# ARDUINO_extension_connectors.net
KiCad netlist of a schematic drawn in Altium Designer
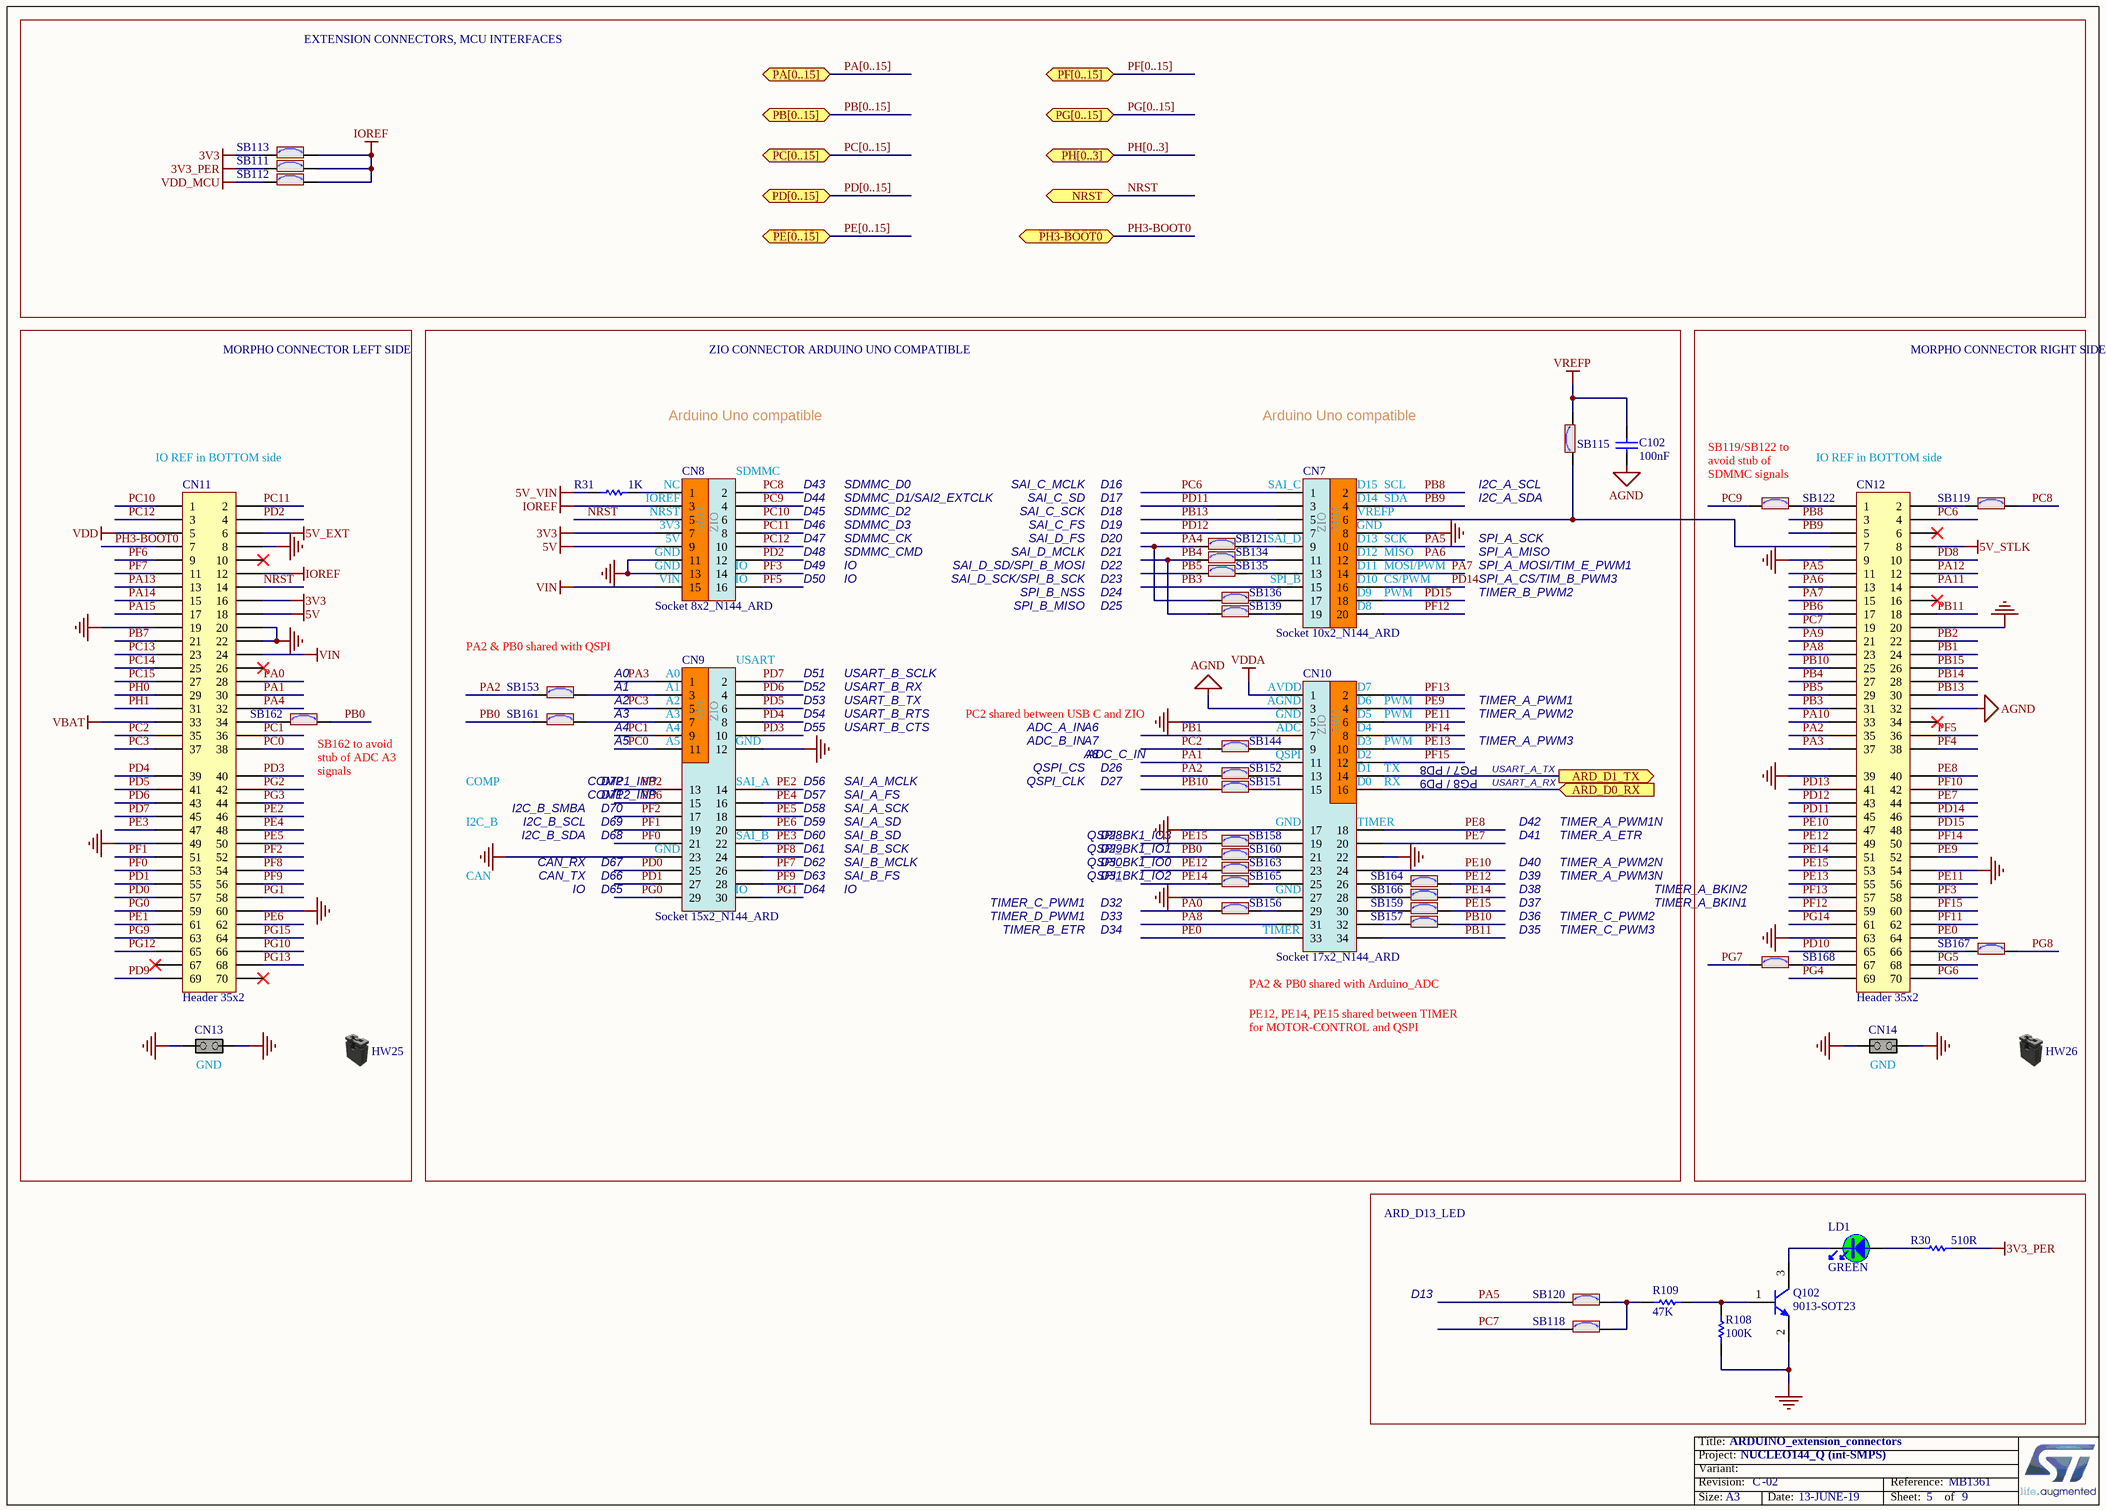
[diagram p0: ARDUINO_extension_connectors.SchDoc]

(export (version "E")
  (design (tool "Eeschema 10.0.6"))
  (components
    (comp (ref "C102")
      (value "100nF")
      (footprint "C0603")
      (description "Capacitor, MLCC, 100nF, 16V, X7R, 10%, 0603, T=0,8mm")
      (fields
        (field (name "INTERNAL_PART_NUMBER") "MCD-00211")
        (field (name "MANUFACTURER_PART_NUMBER") "CC0603KRX7R7BB104")
        (field (name "PROVIDED_BY") "Subcon")
      )
      (libsource (lib "MCD_PARTS_database") (part "Capacitor"))
    )
    (comp (ref "CN7")
      (value "Socket 10x2_N144_ARD")
      (footprint "CON_SAMTEC_SSW-110-23-X-D_N144_ARD")
      (description "Socket, 10x2, 2.54mm, VR, TH, Height 8.51mm/10mm, Low insertion force.")
      (fields
        (field (name "INTERNAL_PART_NUMBER") "MCD-01039")
        (field (name "MANUFACTURER_PART_NUMBER") "SSW-110-23-x-D")
        (field (name "PROVIDED_BY") "Subcon")
      )
      (libsource (lib "MCD_PARTS_database") (part "Socket 10x2_N144_ARD"))
    )
    (comp (ref "CN8")
      (value "Socket 8x2_N144_ARD")
      (footprint "CON_SAMTEC_SSW-108-23-X-D_N144_ARD")
      (description "Socket, 8x2, 2.54mm, VR, TH, Height 8.51mm/10mm, Low insertion force.")
      (fields
        (field (name "INTERNAL_PART_NUMBER") "MCD-01037")
        (field (name "MANUFACTURER_PART_NUMBER") "SSW-108-23-x-D")
        (field (name "PROVIDED_BY") "Subcon")
      )
      (libsource (lib "MCD_PARTS_database") (part "Socket 8x2_N144_ARD"))
    )
    (comp (ref "CN9")
      (value "Socket 15x2_N144_ARD")
      (footprint "CON_SAMTEC_SSW-115-23-X-D_N144_ARD")
      (description "Socket, 15x2, 2.54mm, VR, TH, Height 8.51mm/10mm, Low insertion force.")
      (fields
        (field (name "INTERNAL_PART_NUMBER") "MCD-01040")
        (field (name "MANUFACTURER_PART_NUMBER") "SSW-115-23-x-D")
        (field (name "PROVIDED_BY") "Subcon")
      )
      (libsource (lib "MCD_PARTS_database") (part "Socket 15x2_N144_ARD"))
    )
    (comp (ref "CN10")
      (value "Socket 17x2_N144_ARD")
      (footprint "CON_SAMTEC_SSW-117-23-X-D_N144_ARD")
      (description "Socket, 17x2, 2.54mm, VR, TH, Height 8.51mm/10mm, Low insertion force")
      (fields
        (field (name "INTERNAL_PART_NUMBER") "MCD-01041")
        (field (name "MANUFACTURER_PART_NUMBER") "SSW-117-23-x-D")
        (field (name "PROVIDED_BY") "Subcon")
      )
      (libsource (lib "MCD_PARTS_database") (part "Socket 17x2_N144_ARD"))
    )
    (comp (ref "CN11")
      (value "Header 35x2")
      (footprint "CON_SAMTEC_TSW-135-07-X-D")
      (description "Header, 35x2, 2,54mm, VR, TH, Height 5.84mm/2.54mm")
      (fields
        (field (name "INTERNAL_PART_NUMBER") "MCD-01210")
        (field (name "MANUFACTURER_PART_NUMBER") "TSW-135-07-x-D")
        (field (name "PROVIDED_BY") "Subcon")
      )
      (libsource (lib "MCD_PARTS_database") (part "Header 35x2"))
    )
    (comp (ref "CN12")
      (value "Header 35x2")
      (footprint "CON_SAMTEC_TSW-135-07-X-D")
      (description "Header, 35x2, 2,54mm, VR, TH, Height 5.84mm/2.54mm")
      (fields
        (field (name "INTERNAL_PART_NUMBER") "MCD-01210")
        (field (name "MANUFACTURER_PART_NUMBER") "TSW-135-07-x-D")
        (field (name "PROVIDED_BY") "Subcon")
      )
      (libsource (lib "MCD_PARTS_database") (part "Header 35x2"))
    )
    (comp (ref "CN13")
      (value "~")
      (footprint "CON_SAMTEC_TSW-102-09-X-S")
      (description "Header, 2x1, 2,54mm, VR, TH, Height 5.84mm/10.16mm")
      (fields
        (field (name "INTERNAL_PART_NUMBER") "MCD-00214")
        (field (name "MANUFACTURER_PART_NUMBER") "TSW-102-09-x-S")
        (field (name "PROVIDED_BY") "Subcon")
      )
      (libsource (lib "MCD_PARTS_database") (part "Jumper_Header 2x1"))
    )
    (comp (ref "CN14")
      (value "~")
      (footprint "CON_SAMTEC_TSW-102-09-X-S")
      (description "Header, 2x1, 2,54mm, VR, TH, Height 5.84mm/10.16mm")
      (fields
        (field (name "INTERNAL_PART_NUMBER") "MCD-00214")
        (field (name "MANUFACTURER_PART_NUMBER") "TSW-102-09-x-S")
        (field (name "PROVIDED_BY") "Subcon")
      )
      (libsource (lib "MCD_PARTS_database") (part "Jumper_Header 2x1"))
    )
    (comp (ref "HW25")
      (value "~")
      (description "SHUNT 2.54mm BLACK")
      (fields
        (field (name "INTERNAL_PART_NUMBER") "MCD-00043")
        (field (name "MANUFACTURER_PART_NUMBER") "SNT-100-BK-G")
        (field (name "PROVIDED_BY") "Subcon")
      )
      (libsource (lib "MCD_PARTS_database") (part "Shunt Black 2.54mm"))
    )
    (comp (ref "HW26")
      (value "~")
      (description "SHUNT 2.54mm BLACK")
      (fields
        (field (name "INTERNAL_PART_NUMBER") "MCD-00043")
        (field (name "MANUFACTURER_PART_NUMBER") "SNT-100-BK-G")
        (field (name "PROVIDED_BY") "Subcon")
      )
      (libsource (lib "MCD_PARTS_database") (part "Shunt Black 2.54mm"))
    )
    (comp (ref "LD1")
      (value "GREEN")
      (footprint "LED_0603_GREEN")
      (description "LED, Green, 0603")
      (fields
        (field (name "INTERNAL_PART_NUMBER") "MCD-00050")
        (field (name "MANUFACTURER_PART_NUMBER") "19-213SYGC/S530-E2/TR8")
        (field (name "PROVIDED_BY") "Subcon")
      )
      (libsource (lib "MCD_PARTS_database") (part "LED_green"))
    )
    (comp (ref "Q102")
      (value "9013-SOT23")
      (footprint "NPN_SOT23")
      (description "NPN Bipolar Transistor")
      (fields
        (field (name "INTERNAL_PART_NUMBER") "MCD-00073")
        (field (name "MANUFACTURER_PART_NUMBER") "BSR14")
        (field (name "PROVIDED_BY") "Subcon")
      )
      (libsource (lib "MCD_PARTS_database") (part "9013-SOT23"))
    )
    (comp (ref "R30")
      (value "510R")
      (footprint "R0603")
      (description "Resistor,510R,0603,1%,1/10W")
      (fields
        (field (name "INTERNAL_PART_NUMBER") "MCD-00225")
        (field (name "MANUFACTURER_PART_NUMBER") "RC0603FR-07510RL")
        (field (name "PROVIDED_BY") "Subcon")
      )
      (libsource (lib "MCD_PARTS_database") (part "Resistor"))
    )
    (comp (ref "R31")
      (value "1K")
      (footprint "R0603")
      (description "Resistor,1K,0603,1%,1/10W")
      (fields
        (field (name "INTERNAL_PART_NUMBER") "MCD-00070")
        (field (name "MANUFACTURER_PART_NUMBER") "RC0603FR-071KL")
        (field (name "PROVIDED_BY") "Subcon")
      )
      (libsource (lib "MCD_PARTS_database") (part "Resistor"))
    )
    (comp (ref "R108")
      (value "100K")
      (footprint "R0603")
      (description "Resistor,100K,0603,1%,1/10W")
      (fields
        (field (name "INTERNAL_PART_NUMBER") "MCD-00223")
        (field (name "MANUFACTURER_PART_NUMBER") "RC0603FR-07100KL")
        (field (name "PROVIDED_BY") "Subcon")
      )
      (libsource (lib "MCD_PARTS_database") (part "Resistor"))
    )
    (comp (ref "R109")
      (value "47K")
      (footprint "R0603")
      (description "Resistor,47K,0603,1%,1/10W")
      (fields
        (field (name "INTERNAL_PART_NUMBER") "MCD-00222")
        (field (name "MANUFACTURER_PART_NUMBER") "RC0603FR-0747KL")
        (field (name "PROVIDED_BY") "Subcon")
      )
      (libsource (lib "MCD_PARTS_database") (part "Resistor"))
    )
    (comp (ref "SB111")
      (value "~")
      (footprint "SOLDER-BRIDGE_R0603-0R")
      (description "Solder Bridge ON")
      (fields (field (name "INTERNAL_PART_NUMBER") "MCD-00071") (field (name "PROVIDED_BY") "Subcon"))
      (libsource (lib "MCD_PARTS_database") (part "SB_ON"))
    )
    (comp (ref "SB112")
      (value "~")
      (footprint "SOLDER-BRIDGE_R0603-0R")
      (description "Solder Bridge ON")
      (fields (field (name "INTERNAL_PART_NUMBER") "MCD-00071") (field (name "PROVIDED_BY") "Subcon"))
      (libsource (lib "MCD_PARTS_database") (part "SB_ON"))
    )
    (comp (ref "SB113")
      (value "~")
      (footprint "SOLDER-BRIDGE_R0603-0R")
      (description "Solder Bridge ON")
      (fields (field (name "INTERNAL_PART_NUMBER") "MCD-00071") (field (name "PROVIDED_BY") "Subcon"))
      (libsource (lib "MCD_PARTS_database") (part "SB_ON"))
    )
    (comp (ref "SB115")
      (value "~")
      (footprint "SOLDER-BRIDGE_R0603-0R")
      (description "Solder Bridge ON")
      (fields (field (name "INTERNAL_PART_NUMBER") "MCD-00071") (field (name "PROVIDED_BY") "Subcon"))
      (libsource (lib "") (part "SB_ON_1"))
    )
    (comp (ref "SB118")
      (value "~")
      (footprint "SOLDER-BRIDGE_R0603-0R")
      (description "Solder Bridge ON")
      (fields (field (name "INTERNAL_PART_NUMBER") "MCD-00071") (field (name "PROVIDED_BY") "Subcon"))
      (libsource (lib "MCD_PARTS_database") (part "SB_ON"))
    )
    (comp (ref "SB119")
      (value "~")
      (footprint "SOLDER-BRIDGE_R0603-0R")
      (description "Solder Bridge ON")
      (fields (field (name "INTERNAL_PART_NUMBER") "MCD-00071") (field (name "PROVIDED_BY") "Subcon"))
      (libsource (lib "MCD_PARTS_database") (part "SB_ON"))
    )
    (comp (ref "SB120")
      (value "~")
      (footprint "SOLDER-BRIDGE_R0603-0R")
      (description "Solder Bridge ON")
      (fields (field (name "INTERNAL_PART_NUMBER") "MCD-00071") (field (name "PROVIDED_BY") "Subcon"))
      (libsource (lib "MCD_PARTS_database") (part "SB_ON"))
    )
    (comp (ref "SB121")
      (value "~")
      (footprint "SOLDER-BRIDGE_R0603-0R")
      (description "Solder Bridge ON")
      (fields (field (name "INTERNAL_PART_NUMBER") "MCD-00071") (field (name "PROVIDED_BY") "Subcon"))
      (libsource (lib "MCD_PARTS_database") (part "SB_ON"))
    )
    (comp (ref "SB122")
      (value "~")
      (footprint "SOLDER-BRIDGE_R0603-0R")
      (description "Solder Bridge ON")
      (fields (field (name "INTERNAL_PART_NUMBER") "MCD-00071") (field (name "PROVIDED_BY") "Subcon"))
      (libsource (lib "MCD_PARTS_database") (part "SB_ON"))
    )
    (comp (ref "SB134")
      (value "~")
      (footprint "SOLDER-BRIDGE_R0603-0R")
      (description "Solder Bridge ON")
      (fields (field (name "INTERNAL_PART_NUMBER") "MCD-00071") (field (name "PROVIDED_BY") "Subcon"))
      (libsource (lib "MCD_PARTS_database") (part "SB_ON"))
    )
    (comp (ref "SB135")
      (value "~")
      (footprint "SOLDER-BRIDGE_R0603-0R")
      (description "Solder Bridge ON")
      (fields (field (name "INTERNAL_PART_NUMBER") "MCD-00071") (field (name "PROVIDED_BY") "Subcon"))
      (libsource (lib "MCD_PARTS_database") (part "SB_ON"))
    )
    (comp (ref "SB136")
      (value "~")
      (footprint "SOLDER-BRIDGE_R0603-0R")
      (description "Solder Bridge ON")
      (fields (field (name "INTERNAL_PART_NUMBER") "MCD-00071") (field (name "PROVIDED_BY") "Subcon"))
      (libsource (lib "MCD_PARTS_database") (part "SB_ON"))
    )
    (comp (ref "SB139")
      (value "~")
      (footprint "SOLDER-BRIDGE_R0603-0R")
      (description "Solder Bridge ON")
      (fields (field (name "INTERNAL_PART_NUMBER") "MCD-00071") (field (name "PROVIDED_BY") "Subcon"))
      (libsource (lib "MCD_PARTS_database") (part "SB_ON"))
    )
    (comp (ref "SB144")
      (value "~")
      (footprint "SOLDER-BRIDGE_R0603-0R")
      (description "Solder Bridge ON")
      (fields (field (name "INTERNAL_PART_NUMBER") "MCD-00071") (field (name "PROVIDED_BY") "Subcon"))
      (libsource (lib "MCD_PARTS_database") (part "SB_ON"))
    )
    (comp (ref "SB151")
      (value "~")
      (footprint "SOLDER-BRIDGE_R0603-0R")
      (description "Solder Bridge ON")
      (fields (field (name "INTERNAL_PART_NUMBER") "MCD-00071") (field (name "PROVIDED_BY") "Subcon"))
      (libsource (lib "MCD_PARTS_database") (part "SB_ON"))
    )
    (comp (ref "SB152")
      (value "~")
      (footprint "SOLDER-BRIDGE_R0603-0R")
      (description "Solder Bridge ON")
      (fields (field (name "INTERNAL_PART_NUMBER") "MCD-00071") (field (name "PROVIDED_BY") "Subcon"))
      (libsource (lib "MCD_PARTS_database") (part "SB_ON"))
    )
    (comp (ref "SB153")
      (value "~")
      (footprint "SOLDER-BRIDGE_R0603-0R")
      (description "Solder Bridge ON")
      (fields (field (name "INTERNAL_PART_NUMBER") "MCD-00071") (field (name "PROVIDED_BY") "Subcon"))
      (libsource (lib "MCD_PARTS_database") (part "SB_ON"))
    )
    (comp (ref "SB156")
      (value "~")
      (footprint "SOLDER-BRIDGE_R0603-0R")
      (description "Solder Bridge ON")
      (fields (field (name "INTERNAL_PART_NUMBER") "MCD-00071") (field (name "PROVIDED_BY") "Subcon"))
      (libsource (lib "MCD_PARTS_database") (part "SB_ON"))
    )
    (comp (ref "SB157")
      (value "~")
      (footprint "SOLDER-BRIDGE_R0603-0R")
      (description "Solder Bridge ON")
      (fields (field (name "INTERNAL_PART_NUMBER") "MCD-00071") (field (name "PROVIDED_BY") "Subcon"))
      (libsource (lib "MCD_PARTS_database") (part "SB_ON"))
    )
    (comp (ref "SB158")
      (value "~")
      (footprint "SOLDER-BRIDGE_R0603-0R")
      (description "Solder Bridge ON")
      (fields (field (name "INTERNAL_PART_NUMBER") "MCD-00071") (field (name "PROVIDED_BY") "Subcon"))
      (libsource (lib "MCD_PARTS_database") (part "SB_ON"))
    )
    (comp (ref "SB159")
      (value "~")
      (footprint "SOLDER-BRIDGE_R0603-0R")
      (description "Solder Bridge ON")
      (fields (field (name "INTERNAL_PART_NUMBER") "MCD-00071") (field (name "PROVIDED_BY") "Subcon"))
      (libsource (lib "MCD_PARTS_database") (part "SB_ON"))
    )
    (comp (ref "SB160")
      (value "~")
      (footprint "SOLDER-BRIDGE_R0603-0R")
      (description "Solder Bridge ON")
      (fields (field (name "INTERNAL_PART_NUMBER") "MCD-00071") (field (name "PROVIDED_BY") "Subcon"))
      (libsource (lib "MCD_PARTS_database") (part "SB_ON"))
    )
    (comp (ref "SB161")
      (value "~")
      (footprint "SOLDER-BRIDGE_R0603-0R")
      (description "Solder Bridge ON")
      (fields (field (name "INTERNAL_PART_NUMBER") "MCD-00071") (field (name "PROVIDED_BY") "Subcon"))
      (libsource (lib "MCD_PARTS_database") (part "SB_ON"))
    )
    (comp (ref "SB162")
      (value "~")
      (footprint "SOLDER-BRIDGE_R0603-0R")
      (description "Solder Bridge ON")
      (fields (field (name "INTERNAL_PART_NUMBER") "MCD-00071") (field (name "PROVIDED_BY") "Subcon"))
      (libsource (lib "MCD_PARTS_database") (part "SB_ON"))
    )
    (comp (ref "SB163")
      (value "~")
      (footprint "SOLDER-BRIDGE_R0603-0R")
      (description "Solder Bridge ON")
      (fields (field (name "INTERNAL_PART_NUMBER") "MCD-00071") (field (name "PROVIDED_BY") "Subcon"))
      (libsource (lib "MCD_PARTS_database") (part "SB_ON"))
    )
    (comp (ref "SB164")
      (value "~")
      (footprint "SOLDER-BRIDGE_R0603-0R")
      (description "Solder Bridge ON")
      (fields (field (name "INTERNAL_PART_NUMBER") "MCD-00071") (field (name "PROVIDED_BY") "Subcon"))
      (libsource (lib "MCD_PARTS_database") (part "SB_ON"))
    )
    (comp (ref "SB165")
      (value "~")
      (footprint "SOLDER-BRIDGE_R0603-0R")
      (description "Solder Bridge ON")
      (fields (field (name "INTERNAL_PART_NUMBER") "MCD-00071") (field (name "PROVIDED_BY") "Subcon"))
      (libsource (lib "MCD_PARTS_database") (part "SB_ON"))
    )
    (comp (ref "SB166")
      (value "~")
      (footprint "SOLDER-BRIDGE_R0603-0R")
      (description "Solder Bridge ON")
      (fields (field (name "INTERNAL_PART_NUMBER") "MCD-00071") (field (name "PROVIDED_BY") "Subcon"))
      (libsource (lib "MCD_PARTS_database") (part "SB_ON"))
    )
    (comp (ref "SB167")
      (value "~")
      (footprint "SOLDER-BRIDGE_R0603-0R")
      (description "Solder Bridge ON")
      (fields (field (name "INTERNAL_PART_NUMBER") "MCD-00071") (field (name "PROVIDED_BY") "Subcon"))
      (libsource (lib "MCD_PARTS_database") (part "SB_ON"))
    )
    (comp (ref "SB168")
      (value "~")
      (footprint "SOLDER-BRIDGE_R0603-0R")
      (description "Solder Bridge ON")
      (fields (field (name "INTERNAL_PART_NUMBER") "MCD-00071") (field (name "PROVIDED_BY") "Subcon"))
      (libsource (lib "MCD_PARTS_database") (part "SB_ON"))
    )
  )
  (nets
    (net (code "7") (name "/ARD_D0_RX") (class "Default")
      (node (ref "CN10") (pin "16") (pinfunction "16_16") (pintype "passive"))
    )
    (net (code "8") (name "/ARD_D1_TX") (class "Default")
      (node (ref "CN10") (pin "14") (pinfunction "14_14") (pintype "passive"))
    )
    (net (code "9") (name "/NRST") (class "Default")
      (node (ref "CN11") (pin "14") (pinfunction "14_14") (pintype "passive"))
      (node (ref "CN8") (pin "5") (pinfunction "5_5") (pintype "passive"))
    )
    (net (code "10") (name "/PA0") (class "Default")
      (node (ref "CN11") (pin "28") (pinfunction "28_28") (pintype "passive"))
      (node (ref "SB156") (pin "1") (pinfunction "1_1") (pintype "passive"))
    )
    (net (code "11") (name "/PA1") (class "Default")
      (node (ref "CN10") (pin "11") (pinfunction "11_11") (pintype "passive"))
      (node (ref "CN11") (pin "30") (pinfunction "30_30") (pintype "passive"))
    )
    (net (code "12") (name "/PA2") (class "Default")
      (node (ref "CN12") (pin "35") (pinfunction "35_35") (pintype "passive"))
      (node (ref "SB152") (pin "1") (pinfunction "1_1") (pintype "passive"))
      (node (ref "SB153") (pin "1") (pinfunction "1_1") (pintype "passive"))
    )
    (net (code "13") (name "/PA3") (class "Default")
      (node (ref "CN12") (pin "37") (pinfunction "37_37") (pintype "passive"))
      (node (ref "CN9") (pin "1") (pinfunction "1_1") (pintype "passive"))
    )
    (net (code "14") (name "/PA4") (class "Default")
      (node (ref "CN11") (pin "32") (pinfunction "32_32") (pintype "passive"))
      (node (ref "SB121") (pin "1") (pinfunction "1_1") (pintype "passive"))
      (node (ref "SB136") (pin "1") (pinfunction "1_1") (pintype "passive"))
    )
    (net (code "15") (name "/PA5") (class "Default")
      (node (ref "CN12") (pin "11") (pinfunction "11_11") (pintype "passive"))
      (node (ref "CN7") (pin "10") (pinfunction "10_10") (pintype "passive"))
      (node (ref "SB120") (pin "1") (pinfunction "1_1") (pintype "passive"))
    )
    (net (code "16") (name "/PA6") (class "Default")
      (node (ref "CN12") (pin "13") (pinfunction "13_13") (pintype "passive"))
      (node (ref "CN7") (pin "12") (pinfunction "12_12") (pintype "passive"))
    )
    (net (code "17") (name "/PA7") (class "Default")
      (node (ref "CN12") (pin "15") (pinfunction "15_15") (pintype "passive"))
      (node (ref "CN7") (pin "14") (pinfunction "14_14") (pintype "passive"))
    )
    (net (code "18") (name "/PA8") (class "Default")
      (node (ref "CN10") (pin "31") (pinfunction "31_31") (pintype "passive"))
      (node (ref "CN12") (pin "23") (pinfunction "23_23") (pintype "passive"))
    )
    (net (code "19") (name "/PA9") (class "Default")
      (node (ref "CN12") (pin "21") (pinfunction "21_21") (pintype "passive"))
    )
    (net (code "20") (name "/PA10") (class "Default")
      (node (ref "CN12") (pin "33") (pinfunction "33_33") (pintype "passive"))
    )
    (net (code "21") (name "/PA11") (class "Default")
      (node (ref "CN12") (pin "14") (pinfunction "14_14") (pintype "passive"))
    )
    (net (code "22") (name "/PA12") (class "Default")
      (node (ref "CN12") (pin "12") (pinfunction "12_12") (pintype "passive"))
    )
    (net (code "23") (name "/PA13") (class "Default")
      (node (ref "CN11") (pin "13") (pinfunction "13_13") (pintype "passive"))
    )
    (net (code "24") (name "/PA14") (class "Default")
      (node (ref "CN11") (pin "15") (pinfunction "15_15") (pintype "passive"))
    )
    (net (code "25") (name "/PA15") (class "Default")
      (node (ref "CN11") (pin "17") (pinfunction "17_17") (pintype "passive"))
    )
    (net (code "27") (name "/PB0") (class "Default")
      (node (ref "SB160") (pin "1") (pinfunction "1_1") (pintype "passive"))
      (node (ref "SB161") (pin "1") (pinfunction "1_1") (pintype "passive"))
      (node (ref "SB162") (pin "2") (pinfunction "2_2") (pintype "passive"))
    )
    (net (code "28") (name "/PB1") (class "Default")
      (node (ref "CN10") (pin "7") (pinfunction "7_7") (pintype "passive"))
      (node (ref "CN12") (pin "24") (pinfunction "24_24") (pintype "passive"))
    )
    (net (code "29") (name "/PB2") (class "Default")
      (node (ref "CN12") (pin "22") (pinfunction "22_22") (pintype "passive"))
      (node (ref "CN9") (pin "13") (pinfunction "13_13") (pintype "passive"))
    )
    (net (code "30") (name "/PB3") (class "Default")
      (node (ref "CN12") (pin "31") (pinfunction "31_31") (pintype "passive"))
      (node (ref "CN7") (pin "15") (pinfunction "15_15") (pintype "passive"))
    )
    (net (code "31") (name "/PB4") (class "Default")
      (node (ref "CN12") (pin "27") (pinfunction "27_27") (pintype "passive"))
      (node (ref "SB134") (pin "1") (pinfunction "1_1") (pintype "passive"))
      (node (ref "SB139") (pin "1") (pinfunction "1_1") (pintype "passive"))
    )
    (net (code "32") (name "/PB5") (class "Default")
      (node (ref "CN12") (pin "29") (pinfunction "29_29") (pintype "passive"))
      (node (ref "SB135") (pin "1") (pinfunction "1_1") (pintype "passive"))
    )
    (net (code "33") (name "/PB6") (class "Default")
      (node (ref "CN12") (pin "17") (pinfunction "17_17") (pintype "passive"))
      (node (ref "CN9") (pin "15") (pinfunction "15_15") (pintype "passive"))
    )
    (net (code "34") (name "/PB7") (class "Default")
      (node (ref "CN11") (pin "21") (pinfunction "21_21") (pintype "passive"))
    )
    (net (code "35") (name "/PB8") (class "Default")
      (node (ref "CN12") (pin "3") (pinfunction "3_3") (pintype "passive"))
      (node (ref "CN7") (pin "2") (pinfunction "2_2") (pintype "passive"))
    )
    (net (code "36") (name "/PB9") (class "Default")
      (node (ref "CN12") (pin "5") (pinfunction "5_5") (pintype "passive"))
      (node (ref "CN7") (pin "4") (pinfunction "4_4") (pintype "passive"))
    )
    (net (code "37") (name "/PB10") (class "Default")
      (node (ref "CN12") (pin "25") (pinfunction "25_25") (pintype "passive"))
      (node (ref "SB151") (pin "1") (pinfunction "1_1") (pintype "passive"))
      (node (ref "SB157") (pin "2") (pinfunction "2_2") (pintype "passive"))
    )
    (net (code "38") (name "/PB11") (class "Default")
      (node (ref "CN10") (pin "34") (pinfunction "34_34") (pintype "passive"))
      (node (ref "CN12") (pin "18") (pinfunction "18_18") (pintype "passive"))
    )
    (net (code "39") (name "/PB13") (class "Default")
      (node (ref "CN12") (pin "30") (pinfunction "30_30") (pintype "passive"))
      (node (ref "CN7") (pin "5") (pinfunction "5_5") (pintype "passive"))
    )
    (net (code "40") (name "/PB14") (class "Default")
      (node (ref "CN12") (pin "28") (pinfunction "28_28") (pintype "passive"))
    )
    (net (code "41") (name "/PB15") (class "Default")
      (node (ref "CN12") (pin "26") (pinfunction "26_26") (pintype "passive"))
    )
    (net (code "43") (name "/PC0") (class "Default")
      (node (ref "CN11") (pin "38") (pinfunction "38_38") (pintype "passive"))
      (node (ref "CN9") (pin "11") (pinfunction "11_11") (pintype "passive"))
    )
    (net (code "44") (name "/PC1") (class "Default")
      (node (ref "CN11") (pin "36") (pinfunction "36_36") (pintype "passive"))
      (node (ref "CN9") (pin "9") (pinfunction "9_9") (pintype "passive"))
    )
    (net (code "45") (name "/PC2") (class "Default")
      (node (ref "CN11") (pin "35") (pinfunction "35_35") (pintype "passive"))
      (node (ref "SB144") (pin "1") (pinfunction "1_1") (pintype "passive"))
    )
    (net (code "46") (name "/PC3") (class "Default")
      (node (ref "CN11") (pin "37") (pinfunction "37_37") (pintype "passive"))
      (node (ref "CN9") (pin "5") (pinfunction "5_5") (pintype "passive"))
    )
    (net (code "47") (name "/PC6") (class "Default")
      (node (ref "CN12") (pin "4") (pinfunction "4_4") (pintype "passive"))
      (node (ref "CN7") (pin "1") (pinfunction "1_1") (pintype "passive"))
    )
    (net (code "48") (name "/PC7") (class "Default")
      (node (ref "CN12") (pin "19") (pinfunction "19_19") (pintype "passive"))
      (node (ref "SB118") (pin "1") (pinfunction "1_1") (pintype "passive"))
    )
    (net (code "49") (name "/PC8") (class "Default")
      (node (ref "CN8") (pin "2") (pinfunction "2_2") (pintype "passive"))
      (node (ref "SB119") (pin "2") (pinfunction "2_2") (pintype "passive"))
    )
    (net (code "50") (name "/PC9") (class "Default")
      (node (ref "CN8") (pin "4") (pinfunction "4_4") (pintype "passive"))
      (node (ref "SB122") (pin "1") (pinfunction "1_1") (pintype "passive"))
    )
    (net (code "51") (name "/PC10") (class "Default")
      (node (ref "CN11") (pin "1") (pinfunction "1_1") (pintype "passive"))
      (node (ref "CN8") (pin "6") (pinfunction "6_6") (pintype "passive"))
    )
    (net (code "52") (name "/PC11") (class "Default")
      (node (ref "CN11") (pin "2") (pinfunction "2_2") (pintype "passive"))
      (node (ref "CN8") (pin "8") (pinfunction "8_8") (pintype "passive"))
    )
    (net (code "53") (name "/PC12") (class "Default")
      (node (ref "CN11") (pin "3") (pinfunction "3_3") (pintype "passive"))
      (node (ref "CN8") (pin "10") (pinfunction "10_10") (pintype "passive"))
    )
    (net (code "54") (name "/PC13") (class "Default")
      (node (ref "CN11") (pin "23") (pinfunction "23_23") (pintype "passive"))
    )
    (net (code "55") (name "/PC14") (class "Default")
      (node (ref "CN11") (pin "25") (pinfunction "25_25") (pintype "passive"))
    )
    (net (code "56") (name "/PC15") (class "Default")
      (node (ref "CN11") (pin "27") (pinfunction "27_27") (pintype "passive"))
    )
    (net (code "58") (name "/PD0") (class "Default")
      (node (ref "CN11") (pin "57") (pinfunction "57_57") (pintype "passive"))
      (node (ref "CN9") (pin "25") (pinfunction "25_25") (pintype "passive"))
    )
    (net (code "59") (name "/PD1") (class "Default")
      (node (ref "CN11") (pin "55") (pinfunction "55_55") (pintype "passive"))
      (node (ref "CN9") (pin "27") (pinfunction "27_27") (pintype "passive"))
    )
    (net (code "60") (name "/PD2") (class "Default")
      (node (ref "CN11") (pin "4") (pinfunction "4_4") (pintype "passive"))
      (node (ref "CN8") (pin "12") (pinfunction "12_12") (pintype "passive"))
    )
    (net (code "61") (name "/PD3") (class "Default")
      (node (ref "CN11") (pin "40") (pinfunction "40_40") (pintype "passive"))
      (node (ref "CN9") (pin "10") (pinfunction "10_10") (pintype "passive"))
    )
    (net (code "62") (name "/PD4") (class "Default")
      (node (ref "CN11") (pin "39") (pinfunction "39_39") (pintype "passive"))
      (node (ref "CN9") (pin "8") (pinfunction "8_8") (pintype "passive"))
    )
    (net (code "63") (name "/PD5") (class "Default")
      (node (ref "CN11") (pin "41") (pinfunction "41_41") (pintype "passive"))
      (node (ref "CN9") (pin "6") (pinfunction "6_6") (pintype "passive"))
    )
    (net (code "64") (name "/PD6") (class "Default")
      (node (ref "CN11") (pin "43") (pinfunction "43_43") (pintype "passive"))
      (node (ref "CN9") (pin "4") (pinfunction "4_4") (pintype "passive"))
    )
    (net (code "65") (name "/PD7") (class "Default")
      (node (ref "CN11") (pin "45") (pinfunction "45_45") (pintype "passive"))
      (node (ref "CN9") (pin "2") (pinfunction "2_2") (pintype "passive"))
    )
    (net (code "66") (name "/PD8") (class "Default")
      (node (ref "CN12") (pin "10") (pinfunction "10_10") (pintype "passive"))
    )
    (net (code "67") (name "/PD9") (class "Default")
      (node (ref "CN11") (pin "69") (pinfunction "69_69") (pintype "passive"))
    )
    (net (code "68") (name "/PD10") (class "Default")
      (node (ref "CN12") (pin "65") (pinfunction "65_65") (pintype "passive"))
    )
    (net (code "69") (name "/PD11") (class "Default")
      (node (ref "CN12") (pin "45") (pinfunction "45_45") (pintype "passive"))
      (node (ref "CN7") (pin "3") (pinfunction "3_3") (pintype "passive"))
    )
    (net (code "70") (name "/PD12") (class "Default")
      (node (ref "CN12") (pin "43") (pinfunction "43_43") (pintype "passive"))
      (node (ref "CN7") (pin "7") (pinfunction "7_7") (pintype "passive"))
    )
    (net (code "71") (name "/PD13") (class "Default")
      (node (ref "CN12") (pin "41") (pinfunction "41_41") (pintype "passive"))
    )
    (net (code "72") (name "/PD14") (class "Default")
      (node (ref "CN12") (pin "46") (pinfunction "46_46") (pintype "passive"))
      (node (ref "CN7") (pin "16") (pinfunction "16_16") (pintype "passive"))
    )
    (net (code "73") (name "/PD15") (class "Default")
      (node (ref "CN12") (pin "48") (pinfunction "48_48") (pintype "passive"))
      (node (ref "CN7") (pin "18") (pinfunction "18_18") (pintype "passive"))
    )
    (net (code "75") (name "/PE0") (class "Default")
      (node (ref "CN10") (pin "33") (pinfunction "33_33") (pintype "passive"))
      (node (ref "CN12") (pin "64") (pinfunction "64_64") (pintype "passive"))
    )
    (net (code "76") (name "/PE1") (class "Default")
      (node (ref "CN11") (pin "61") (pinfunction "61_61") (pintype "passive"))
    )
    (net (code "77") (name "/PE2") (class "Default")
      (node (ref "CN11") (pin "46") (pinfunction "46_46") (pintype "passive"))
      (node (ref "CN9") (pin "14") (pinfunction "14_14") (pintype "passive"))
    )
    (net (code "78") (name "/PE3") (class "Default")
      (node (ref "CN11") (pin "47") (pinfunction "47_47") (pintype "passive"))
      (node (ref "CN9") (pin "22") (pinfunction "22_22") (pintype "passive"))
    )
    (net (code "79") (name "/PE4") (class "Default")
      (node (ref "CN11") (pin "48") (pinfunction "48_48") (pintype "passive"))
      (node (ref "CN9") (pin "16") (pinfunction "16_16") (pintype "passive"))
    )
    (net (code "80") (name "/PE5") (class "Default")
      (node (ref "CN11") (pin "50") (pinfunction "50_50") (pintype "passive"))
      (node (ref "CN9") (pin "18") (pinfunction "18_18") (pintype "passive"))
    )
    (net (code "81") (name "/PE6") (class "Default")
      (node (ref "CN11") (pin "62") (pinfunction "62_62") (pintype "passive"))
      (node (ref "CN9") (pin "20") (pinfunction "20_20") (pintype "passive"))
    )
    (net (code "82") (name "/PE7") (class "Default")
      (node (ref "CN10") (pin "20") (pinfunction "20_20") (pintype "passive"))
      (node (ref "CN12") (pin "44") (pinfunction "44_44") (pintype "passive"))
    )
    (net (code "83") (name "/PE8") (class "Default")
      (node (ref "CN10") (pin "18") (pinfunction "18_18") (pintype "passive"))
      (node (ref "CN12") (pin "40") (pinfunction "40_40") (pintype "passive"))
    )
    (net (code "84") (name "/PE9") (class "Default")
      (node (ref "CN10") (pin "4") (pinfunction "4_4") (pintype "passive"))
      (node (ref "CN12") (pin "52") (pinfunction "52_52") (pintype "passive"))
    )
    (net (code "85") (name "/PE10") (class "Default")
      (node (ref "CN10") (pin "24") (pinfunction "24_24") (pintype "passive"))
      (node (ref "CN12") (pin "47") (pinfunction "47_47") (pintype "passive"))
    )
    (net (code "86") (name "/PE11") (class "Default")
      (node (ref "CN10") (pin "6") (pinfunction "6_6") (pintype "passive"))
      (node (ref "CN12") (pin "56") (pinfunction "56_56") (pintype "passive"))
    )
    (net (code "87") (name "/PE12") (class "Default")
      (node (ref "CN12") (pin "49") (pinfunction "49_49") (pintype "passive"))
      (node (ref "SB163") (pin "1") (pinfunction "1_1") (pintype "passive"))
      (node (ref "SB164") (pin "2") (pinfunction "2_2") (pintype "passive"))
    )
    (net (code "88") (name "/PE13") (class "Default")
      (node (ref "CN10") (pin "10") (pinfunction "10_10") (pintype "passive"))
      (node (ref "CN12") (pin "55") (pinfunction "55_55") (pintype "passive"))
    )
    (net (code "89") (name "/PE14") (class "Default")
      (node (ref "CN12") (pin "51") (pinfunction "51_51") (pintype "passive"))
      (node (ref "SB165") (pin "1") (pinfunction "1_1") (pintype "passive"))
      (node (ref "SB166") (pin "2") (pinfunction "2_2") (pintype "passive"))
    )
    (net (code "90") (name "/PE15") (class "Default")
      (node (ref "CN12") (pin "53") (pinfunction "53_53") (pintype "passive"))
      (node (ref "SB158") (pin "1") (pinfunction "1_1") (pintype "passive"))
      (node (ref "SB159") (pin "2") (pinfunction "2_2") (pintype "passive"))
    )
    (net (code "92") (name "/PF0") (class "Default")
      (node (ref "CN11") (pin "53") (pinfunction "53_53") (pintype "passive"))
      (node (ref "CN9") (pin "21") (pinfunction "21_21") (pintype "passive"))
    )
    (net (code "93") (name "/PF1") (class "Default")
      (node (ref "CN11") (pin "51") (pinfunction "51_51") (pintype "passive"))
      (node (ref "CN9") (pin "19") (pinfunction "19_19") (pintype "passive"))
    )
    (net (code "94") (name "/PF2") (class "Default")
      (node (ref "CN11") (pin "52") (pinfunction "52_52") (pintype "passive"))
      (node (ref "CN9") (pin "17") (pinfunction "17_17") (pintype "passive"))
    )
    (net (code "95") (name "/PF3") (class "Default")
      (node (ref "CN12") (pin "58") (pinfunction "58_58") (pintype "passive"))
      (node (ref "CN8") (pin "14") (pinfunction "14_14") (pintype "passive"))
    )
    (net (code "96") (name "/PF4") (class "Default")
      (node (ref "CN12") (pin "38") (pinfunction "38_38") (pintype "passive"))
    )
    (net (code "97") (name "/PF5") (class "Default")
      (node (ref "CN12") (pin "36") (pinfunction "36_36") (pintype "passive"))
      (node (ref "CN8") (pin "16") (pinfunction "16_16") (pintype "passive"))
    )
    (net (code "98") (name "/PF6") (class "Default")
      (node (ref "CN11") (pin "9") (pinfunction "9_9") (pintype "passive"))
    )
    (net (code "99") (name "/PF7") (class "Default")
      (node (ref "CN11") (pin "11") (pinfunction "11_11") (pintype "passive"))
      (node (ref "CN9") (pin "26") (pinfunction "26_26") (pintype "passive"))
    )
    (net (code "100") (name "/PF8") (class "Default")
      (node (ref "CN11") (pin "54") (pinfunction "54_54") (pintype "passive"))
      (node (ref "CN9") (pin "24") (pinfunction "24_24") (pintype "passive"))
    )
    (net (code "101") (name "/PF9") (class "Default")
      (node (ref "CN11") (pin "56") (pinfunction "56_56") (pintype "passive"))
      (node (ref "CN9") (pin "28") (pinfunction "28_28") (pintype "passive"))
    )
    (net (code "102") (name "/PF10") (class "Default")
      (node (ref "CN12") (pin "42") (pinfunction "42_42") (pintype "passive"))
    )
    (net (code "103") (name "/PF11") (class "Default")
      (node (ref "CN12") (pin "62") (pinfunction "62_62") (pintype "passive"))
    )
    (net (code "104") (name "/PF12") (class "Default")
      (node (ref "CN12") (pin "59") (pinfunction "59_59") (pintype "passive"))
      (node (ref "CN7") (pin "20") (pinfunction "20_20") (pintype "passive"))
    )
    (net (code "105") (name "/PF13") (class "Default")
      (node (ref "CN10") (pin "2") (pinfunction "2_2") (pintype "passive"))
      (node (ref "CN12") (pin "57") (pinfunction "57_57") (pintype "passive"))
    )
    (net (code "106") (name "/PF14") (class "Default")
      (node (ref "CN10") (pin "8") (pinfunction "8_8") (pintype "passive"))
      (node (ref "CN12") (pin "50") (pinfunction "50_50") (pintype "passive"))
    )
    (net (code "107") (name "/PF15") (class "Default")
      (node (ref "CN10") (pin "12") (pinfunction "12_12") (pintype "passive"))
      (node (ref "CN12") (pin "60") (pinfunction "60_60") (pintype "passive"))
    )
    (net (code "109") (name "/PG0") (class "Default")
      (node (ref "CN11") (pin "59") (pinfunction "59_59") (pintype "passive"))
      (node (ref "CN9") (pin "29") (pinfunction "29_29") (pintype "passive"))
    )
    (net (code "110") (name "/PG1") (class "Default")
      (node (ref "CN11") (pin "58") (pinfunction "58_58") (pintype "passive"))
      (node (ref "CN9") (pin "30") (pinfunction "30_30") (pintype "passive"))
    )
    (net (code "111") (name "/PG2") (class "Default")
      (node (ref "CN11") (pin "42") (pinfunction "42_42") (pintype "passive"))
    )
    (net (code "112") (name "/PG3") (class "Default")
      (node (ref "CN11") (pin "44") (pinfunction "44_44") (pintype "passive"))
    )
    (net (code "113") (name "/PG4") (class "Default")
      (node (ref "CN12") (pin "69") (pinfunction "69_69") (pintype "passive"))
    )
    (net (code "114") (name "/PG5") (class "Default")
      (node (ref "CN12") (pin "68") (pinfunction "68_68") (pintype "passive"))
    )
    (net (code "115") (name "/PG6") (class "Default")
      (node (ref "CN12") (pin "70") (pinfunction "70_70") (pintype "passive"))
    )
    (net (code "116") (name "/PG7") (class "Default")
      (node (ref "SB168") (pin "1") (pinfunction "1_1") (pintype "passive"))
    )
    (net (code "117") (name "/PG8") (class "Default")
      (node (ref "SB167") (pin "2") (pinfunction "2_2") (pintype "passive"))
    )
    (net (code "118") (name "/PG9") (class "Default")
      (node (ref "CN11") (pin "63") (pinfunction "63_63") (pintype "passive"))
    )
    (net (code "119") (name "/PG10") (class "Default")
      (node (ref "CN11") (pin "66") (pinfunction "66_66") (pintype "passive"))
    )
    (net (code "120") (name "/PG12") (class "Default")
      (node (ref "CN11") (pin "65") (pinfunction "65_65") (pintype "passive"))
    )
    (net (code "121") (name "/PG13") (class "Default")
      (node (ref "CN11") (pin "68") (pinfunction "68_68") (pintype "passive"))
    )
    (net (code "122") (name "/PG14") (class "Default")
      (node (ref "CN12") (pin "61") (pinfunction "61_61") (pintype "passive"))
    )
    (net (code "123") (name "/PG15") (class "Default")
      (node (ref "CN11") (pin "64") (pinfunction "64_64") (pintype "passive"))
    )
    (net (code "125") (name "/PH0") (class "Default")
      (node (ref "CN11") (pin "29") (pinfunction "29_29") (pintype "passive"))
    )
    (net (code "126") (name "/PH1") (class "Default")
      (node (ref "CN11") (pin "31") (pinfunction "31_31") (pintype "passive"))
    )
    (net (code "127") (name "/PH3-BOOT0") (class "Default")
      (node (ref "CN11") (pin "7") (pinfunction "7_7") (pintype "passive"))
    )
    (net (code "129") (name "3V3") (class "Default")
      (node (ref "CN11") (pin "16") (pinfunction "16_16") (pintype "passive"))
      (node (ref "CN8") (pin "7") (pinfunction "7_7") (pintype "passive"))
      (node (ref "SB113") (pin "1") (pinfunction "1_1") (pintype "passive"))
    )
    (net (code "130") (name "3V3_PER") (class "Default")
      (node (ref "R30") (pin "2") (pinfunction "2_2") (pintype "passive"))
      (node (ref "SB111") (pin "1") (pinfunction "1_1") (pintype "passive"))
    )
    (net (code "131") (name "5V") (class "Default")
      (node (ref "CN11") (pin "18") (pinfunction "18_18") (pintype "passive"))
      (node (ref "CN8") (pin "9") (pinfunction "9_9") (pintype "passive"))
    )
    (net (code "132") (name "5V_EXT") (class "Default")
      (node (ref "CN11") (pin "6") (pinfunction "6_6") (pintype "passive"))
    )
    (net (code "133") (name "5V_STLK") (class "Default")
      (node (ref "CN12") (pin "8") (pinfunction "8_8") (pintype "passive"))
    )
    (net (code "134") (name "5V_VIN") (class "Default")
      (node (ref "R31") (pin "2") (pinfunction "2_2") (pintype "passive"))
    )
    (net (code "135") (name "AGND") (class "Default")
      (node (ref "C102") (pin "1") (pinfunction "1_1") (pintype "passive"))
      (node (ref "CN10") (pin "3") (pinfunction "3_3") (pintype "passive"))
      (node (ref "CN12") (pin "32") (pinfunction "32_32") (pintype "passive"))
    )
    (net (code "136") (name "GND") (class "Default")
      (node (ref "CN10") (pin "17") (pinfunction "17_17") (pintype "passive"))
      (node (ref "CN10") (pin "22") (pinfunction "22_22") (pintype "passive"))
      (node (ref "CN10") (pin "27") (pinfunction "27_27") (pintype "passive"))
      (node (ref "CN10") (pin "5") (pinfunction "5_5") (pintype "passive"))
      (node (ref "CN11") (pin "19") (pinfunction "19_19") (pintype "passive"))
      (node (ref "CN11") (pin "20") (pinfunction "20_20") (pintype "passive"))
      (node (ref "CN11") (pin "22") (pinfunction "22_22") (pintype "passive"))
      (node (ref "CN11") (pin "49") (pinfunction "49_49") (pintype "passive"))
      (node (ref "CN11") (pin "60") (pinfunction "60_60") (pintype "passive"))
      (node (ref "CN11") (pin "8") (pinfunction "8_8") (pintype "passive"))
      (node (ref "CN12") (pin "20") (pinfunction "20_20") (pintype "passive"))
      (node (ref "CN12") (pin "39") (pinfunction "39_39") (pintype "passive"))
      (node (ref "CN12") (pin "54") (pinfunction "54_54") (pintype "passive"))
      (node (ref "CN12") (pin "63") (pinfunction "63_63") (pintype "passive"))
      (node (ref "CN12") (pin "9") (pinfunction "9_9") (pintype "passive"))
      (node (ref "CN13") (pin "1") (pinfunction "COMMON_1") (pintype "passive"))
      (node (ref "CN13") (pin "2") (pinfunction "NO_2") (pintype "passive"))
      (node (ref "CN14") (pin "1") (pinfunction "COMMON_1") (pintype "passive"))
      (node (ref "CN14") (pin "2") (pinfunction "NO_2") (pintype "passive"))
      (node (ref "CN7") (pin "8") (pinfunction "8_8") (pintype "passive"))
      (node (ref "CN8") (pin "11") (pinfunction "11_11") (pintype "passive"))
      (node (ref "CN8") (pin "13") (pinfunction "13_13") (pintype "passive"))
      (node (ref "CN9") (pin "12") (pinfunction "12_12") (pintype "passive"))
      (node (ref "CN9") (pin "23") (pinfunction "23_23") (pintype "passive"))
      (node (ref "Q102") (pin "2") (pinfunction "E_2") (pintype "passive"))
      (node (ref "R108") (pin "1") (pinfunction "1_1") (pintype "passive"))
    )
    (net (code "137") (name "IOREF") (class "Default")
      (node (ref "CN11") (pin "12") (pinfunction "12_12") (pintype "passive"))
      (node (ref "CN8") (pin "3") (pinfunction "3_3") (pintype "passive"))
      (node (ref "SB111") (pin "2") (pinfunction "2_2") (pintype "passive"))
      (node (ref "SB112") (pin "2") (pinfunction "2_2") (pintype "passive"))
      (node (ref "SB113") (pin "2") (pinfunction "2_2") (pintype "passive"))
    )
    (net (code "138") (name "Net-(CN7-Pad9)") (class "Default")
      (node (ref "CN7") (pin "9") (pinfunction "9_9") (pintype "passive"))
      (node (ref "SB121") (pin "2") (pinfunction "2_2") (pintype "passive"))
    )
    (net (code "139") (name "Net-(CN7-Pad11)") (class "Default")
      (node (ref "CN7") (pin "11") (pinfunction "11_11") (pintype "passive"))
      (node (ref "SB134") (pin "2") (pinfunction "2_2") (pintype "passive"))
    )
    (net (code "140") (name "Net-(CN7-Pad13)") (class "Default")
      (node (ref "CN7") (pin "13") (pinfunction "13_13") (pintype "passive"))
      (node (ref "SB135") (pin "2") (pinfunction "2_2") (pintype "passive"))
    )
    (net (code "141") (name "Net-(CN7-Pad17)") (class "Default")
      (node (ref "CN7") (pin "17") (pinfunction "17_17") (pintype "passive"))
      (node (ref "SB136") (pin "2") (pinfunction "2_2") (pintype "passive"))
    )
    (net (code "142") (name "Net-(CN7-Pad19)") (class "Default")
      (node (ref "CN7") (pin "19") (pinfunction "19_19") (pintype "passive"))
      (node (ref "SB139") (pin "2") (pinfunction "2_2") (pintype "passive"))
    )
    (net (code "143") (name "Net-(CN8-Pad1)") (class "Default")
      (node (ref "CN8") (pin "1") (pinfunction "1_1") (pintype "passive"))
      (node (ref "R31") (pin "1") (pinfunction "1_1") (pintype "passive"))
    )
    (net (code "144") (name "Net-(CN9-Pad3)") (class "Default")
      (node (ref "CN9") (pin "3") (pinfunction "3_3") (pintype "passive"))
      (node (ref "SB153") (pin "2") (pinfunction "2_2") (pintype "passive"))
    )
    (net (code "145") (name "Net-(CN9-Pad7)") (class "Default")
      (node (ref "CN9") (pin "7") (pinfunction "7_7") (pintype "passive"))
      (node (ref "SB161") (pin "2") (pinfunction "2_2") (pintype "passive"))
    )
    (net (code "146") (name "Net-(CN10-Pad9)") (class "Default")
      (node (ref "CN10") (pin "9") (pinfunction "9_9") (pintype "passive"))
      (node (ref "SB144") (pin "2") (pinfunction "2_2") (pintype "passive"))
    )
    (net (code "147") (name "Net-(CN10-Pad13)") (class "Default")
      (node (ref "CN10") (pin "13") (pinfunction "13_13") (pintype "passive"))
      (node (ref "SB152") (pin "2") (pinfunction "2_2") (pintype "passive"))
    )
    (net (code "148") (name "Net-(CN10-Pad15)") (class "Default")
      (node (ref "CN10") (pin "15") (pinfunction "15_15") (pintype "passive"))
      (node (ref "SB151") (pin "2") (pinfunction "2_2") (pintype "passive"))
    )
    (net (code "149") (name "Net-(CN10-Pad19)") (class "Default")
      (node (ref "CN10") (pin "19") (pinfunction "19_19") (pintype "passive"))
      (node (ref "SB158") (pin "2") (pinfunction "2_2") (pintype "passive"))
    )
    (net (code "150") (name "Net-(CN10-Pad21)") (class "Default")
      (node (ref "CN10") (pin "21") (pinfunction "21_21") (pintype "passive"))
      (node (ref "SB160") (pin "2") (pinfunction "2_2") (pintype "passive"))
    )
    (net (code "151") (name "Net-(CN10-Pad23)") (class "Default")
      (node (ref "CN10") (pin "23") (pinfunction "23_23") (pintype "passive"))
      (node (ref "SB163") (pin "2") (pinfunction "2_2") (pintype "passive"))
    )
    (net (code "152") (name "Net-(CN10-Pad25)") (class "Default")
      (node (ref "CN10") (pin "25") (pinfunction "25_25") (pintype "passive"))
      (node (ref "SB165") (pin "2") (pinfunction "2_2") (pintype "passive"))
    )
    (net (code "153") (name "Net-(CN10-Pad26)") (class "Default")
      (node (ref "CN10") (pin "26") (pinfunction "26_26") (pintype "passive"))
      (node (ref "SB164") (pin "1") (pinfunction "1_1") (pintype "passive"))
    )
    (net (code "154") (name "Net-(CN10-Pad28)") (class "Default")
      (node (ref "CN10") (pin "28") (pinfunction "28_28") (pintype "passive"))
      (node (ref "SB166") (pin "1") (pinfunction "1_1") (pintype "passive"))
    )
    (net (code "155") (name "Net-(CN10-Pad29)") (class "Default")
      (node (ref "CN10") (pin "29") (pinfunction "29_29") (pintype "passive"))
      (node (ref "SB156") (pin "2") (pinfunction "2_2") (pintype "passive"))
    )
    (net (code "156") (name "Net-(CN10-Pad30)") (class "Default")
      (node (ref "CN10") (pin "30") (pinfunction "30_30") (pintype "passive"))
      (node (ref "SB159") (pin "1") (pinfunction "1_1") (pintype "passive"))
    )
    (net (code "157") (name "Net-(CN10-Pad32)") (class "Default")
      (node (ref "CN10") (pin "32") (pinfunction "32_32") (pintype "passive"))
      (node (ref "SB157") (pin "1") (pinfunction "1_1") (pintype "passive"))
    )
    (net (code "158") (name "Net-(CN11-Pad34)") (class "Default")
      (node (ref "CN11") (pin "34") (pinfunction "34_34") (pintype "passive"))
      (node (ref "SB162") (pin "1") (pinfunction "1_1") (pintype "passive"))
    )
    (net (code "159") (name "Net-(CN12-Pad1)") (class "Default")
      (node (ref "CN12") (pin "1") (pinfunction "1_1") (pintype "passive"))
      (node (ref "SB122") (pin "2") (pinfunction "2_2") (pintype "passive"))
    )
    (net (code "160") (name "Net-(CN12-Pad2)") (class "Default")
      (node (ref "CN12") (pin "2") (pinfunction "2_2") (pintype "passive"))
      (node (ref "SB119") (pin "1") (pinfunction "1_1") (pintype "passive"))
    )
    (net (code "161") (name "Net-(CN12-Pad7)") (class "Default")
      (node (ref "CN12") (pin "7") (pinfunction "7_7") (pintype "passive"))
      (node (ref "CN7") (pin "6") (pinfunction "6_6") (pintype "passive"))
      (node (ref "SB115") (pin "1") (pinfunction "1_1") (pintype "passive"))
    )
    (net (code "162") (name "Net-(CN12-Pad66)") (class "Default")
      (node (ref "CN12") (pin "66") (pinfunction "66_66") (pintype "passive"))
      (node (ref "SB167") (pin "1") (pinfunction "1_1") (pintype "passive"))
    )
    (net (code "163") (name "Net-(CN12-Pad67)") (class "Default")
      (node (ref "CN12") (pin "67") (pinfunction "67_67") (pintype "passive"))
      (node (ref "SB168") (pin "2") (pinfunction "2_2") (pintype "passive"))
    )
    (net (code "164") (name "Net-(LD1-Pad1)") (class "Default")
      (node (ref "LD1") (pin "1") (pintype "passive"))
      (node (ref "R30") (pin "1") (pinfunction "1_1") (pintype "passive"))
    )
    (net (code "165") (name "Net-(Q102-B)") (class "Default")
      (node (ref "Q102") (pin "1") (pinfunction "B_1") (pintype "passive"))
      (node (ref "R108") (pin "2") (pinfunction "2_2") (pintype "passive"))
      (node (ref "R109") (pin "2") (pinfunction "2_2") (pintype "passive"))
    )
    (net (code "166") (name "Net-(Q102-C)") (class "Default")
      (node (ref "LD1") (pin "2") (pintype "passive"))
      (node (ref "Q102") (pin "3") (pinfunction "C_3") (pintype "passive"))
    )
    (net (code "167") (name "Net-(R109-Pad1)") (class "Default")
      (node (ref "R109") (pin "1") (pinfunction "1_1") (pintype "passive"))
      (node (ref "SB118") (pin "2") (pinfunction "2_2") (pintype "passive"))
      (node (ref "SB120") (pin "2") (pinfunction "2_2") (pintype "passive"))
    )
    (net (code "168") (name "VBAT") (class "Default")
      (node (ref "CN11") (pin "33") (pinfunction "33_33") (pintype "passive"))
    )
    (net (code "169") (name "VDD") (class "Default")
      (node (ref "CN11") (pin "5") (pinfunction "5_5") (pintype "passive"))
    )
    (net (code "170") (name "VDDA") (class "Default")
      (node (ref "CN10") (pin "1") (pinfunction "1_1") (pintype "passive"))
    )
    (net (code "171") (name "VDD_MCU") (class "Default")
      (node (ref "SB112") (pin "1") (pinfunction "1_1") (pintype "passive"))
    )
    (net (code "172") (name "VIN") (class "Default")
      (node (ref "CN11") (pin "24") (pinfunction "24_24") (pintype "passive"))
      (node (ref "CN8") (pin "15") (pinfunction "15_15") (pintype "passive"))
    )
    (net (code "173") (name "VREFP") (class "Default")
      (node (ref "C102") (pin "2") (pinfunction "2_2") (pintype "passive"))
      (node (ref "SB115") (pin "2") (pinfunction "2_2") (pintype "passive"))
    )
    (net (code "174") (name "unconnected-(CN11-Pad10)") (class "Default")
      (node (ref "CN11") (pin "10") (pinfunction "10_10") (pintype "passive+no_connect"))
    )
    (net (code "175") (name "unconnected-(CN11-Pad26)") (class "Default")
      (node (ref "CN11") (pin "26") (pinfunction "26_26") (pintype "passive+no_connect"))
    )
    (net (code "176") (name "unconnected-(CN11-Pad67)") (class "Default")
      (node (ref "CN11") (pin "67") (pinfunction "67_67") (pintype "passive+no_connect"))
    )
    (net (code "177") (name "unconnected-(CN11-Pad70)") (class "Default")
      (node (ref "CN11") (pin "70") (pinfunction "70_70") (pintype "passive+no_connect"))
    )
    (net (code "178") (name "unconnected-(CN12-Pad6)") (class "Default")
      (node (ref "CN12") (pin "6") (pinfunction "6_6") (pintype "passive+no_connect"))
    )
    (net (code "179") (name "unconnected-(CN12-Pad16)") (class "Default")
      (node (ref "CN12") (pin "16") (pinfunction "16_16") (pintype "passive+no_connect"))
    )
    (net (code "180") (name "unconnected-(CN12-Pad34)") (class "Default")
      (node (ref "CN12") (pin "34") (pinfunction "34_34") (pintype "passive+no_connect"))
    )
  )
)
